# bcd_board.net
KiCad netlist of a schematic drawn in EAGLE
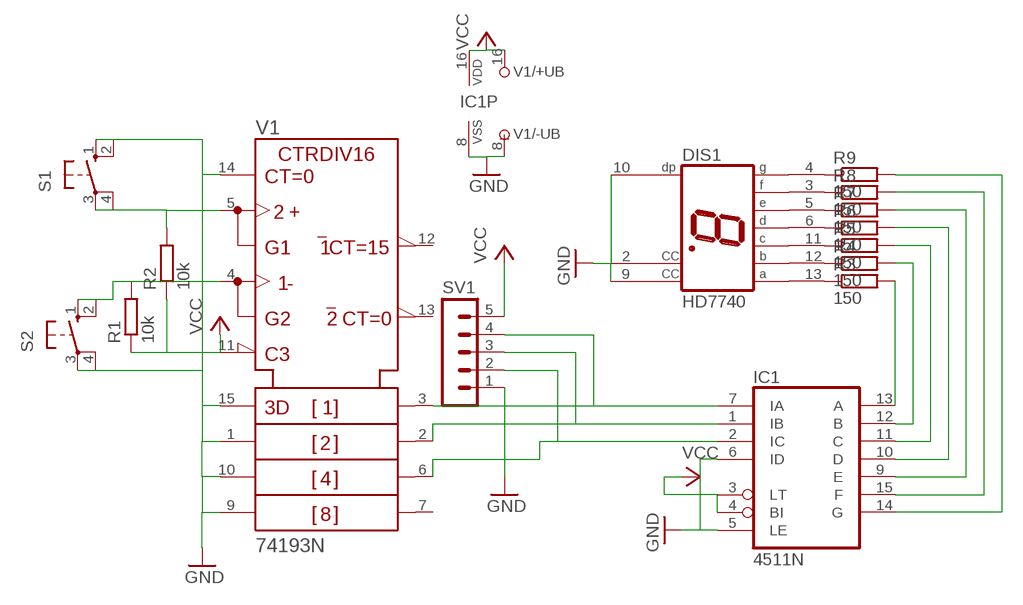
[diagram p0: schematic, sheet 1]

(export (version "E")
  (design (tool "Eeschema 10.0.6"))
  (components
    (comp (ref "DIS1")
      (value "HD7740")
      (footprint "eagle-import:HD7730")
      (libsource (lib "eagle-import") (part "HD7740"))
    )
    (comp (ref "IC1")
      (value "4511N")
      (footprint "eagle-import:DIL16")
      (libsource (lib "eagle-import") (part "4511N"))
    )
    (comp (ref "R1")
      (value "10k")
      (footprint "eagle-import:0204_7")
      (libsource (lib "eagle-import") (part "R-EU_0204/7"))
    )
    (comp (ref "R2")
      (value "10k")
      (footprint "eagle-import:0204_7")
      (libsource (lib "eagle-import") (part "R-EU_0204/7"))
    )
    (comp (ref "R3")
      (value "150")
      (footprint "eagle-import:0204_7")
      (libsource (lib "eagle-import") (part "R-EU_0204/7"))
    )
    (comp (ref "R4")
      (value "150")
      (footprint "eagle-import:0204_7")
      (libsource (lib "eagle-import") (part "R-EU_0204/7"))
    )
    (comp (ref "R5")
      (value "150")
      (footprint "eagle-import:0204_7")
      (libsource (lib "eagle-import") (part "R-EU_0204/7"))
    )
    (comp (ref "R6")
      (value "150")
      (footprint "eagle-import:0204_7")
      (libsource (lib "eagle-import") (part "R-EU_0204/7"))
    )
    (comp (ref "R7")
      (value "150")
      (footprint "eagle-import:0204_7")
      (libsource (lib "eagle-import") (part "R-EU_0204/7"))
    )
    (comp (ref "R8")
      (value "150")
      (footprint "eagle-import:0204_7")
      (libsource (lib "eagle-import") (part "R-EU_0204/7"))
    )
    (comp (ref "R9")
      (value "150")
      (footprint "eagle-import:0204_7")
      (libsource (lib "eagle-import") (part "R-EU_0204/7"))
    )
    (comp (ref "S1")
      (value "10-XX")
      (footprint "eagle-import:B3F-10XX")
      (fields (field (name "MPN") "B3F-1000"))
      (libsource (lib "eagle-import") (part "10-XX"))
    )
    (comp (ref "S2")
      (value "10-XX")
      (footprint "eagle-import:B3F-10XX")
      (fields (field (name "MPN") "B3F-1000"))
      (libsource (lib "eagle-import") (part "10-XX"))
    )
    (comp (ref "SV1")
      (value "MA05-1")
      (footprint "eagle-import:MA05-1")
      (libsource (lib "eagle-import") (part "MA05-1"))
    )
    (comp (ref "V1")
      (value "74193N")
      (footprint "eagle-import:DIL16")
      (libsource (lib "eagle-import") (part "74193N"))
    )
  )
  (nets
    (net (code "1") (name "GND") (class "Default")
      (node (ref "DIS1") (pin "10") (pinfunction "DP_10") (pintype "passive"))
      (node (ref "DIS1") (pin "2") (pinfunction "CC_2") (pintype "passive"))
      (node (ref "DIS1") (pin "9") (pinfunction "CC_9") (pintype "passive"))
      (node (ref "IC1") (pin "5") (pinfunction "LE_5") (pintype "input"))
      (node (ref "IC1") (pin "6") (pinfunction "ID_6") (pintype "input"))
      (node (ref "IC1") (pin "8") (pinfunction "VSS_8") (pintype "power_in"))
      (node (ref "S1") (pin "1") (pinfunction "S_1") (pintype "passive"))
      (node (ref "S1") (pin "2") (pinfunction "S1_2") (pintype "passive"))
      (node (ref "S2") (pin "3") (pinfunction "P_3") (pintype "passive"))
      (node (ref "S2") (pin "4") (pinfunction "P1_4") (pintype "passive"))
      (node (ref "SV1") (pin "1") (pinfunction "1_1") (pintype "passive"))
      (node (ref "V1") (pin "1") (pinfunction "B_1") (pintype "input"))
      (node (ref "V1") (pin "10") (pinfunction "C_10") (pintype "input"))
      (node (ref "V1") (pin "14") (pinfunction "CLR_14") (pintype "input"))
      (node (ref "V1") (pin "15") (pinfunction "A_15") (pintype "input"))
      (node (ref "V1") (pin "8") (pinfunction "-UB_8") (pintype "power_in"))
      (node (ref "V1") (pin "9") (pinfunction "D_9") (pintype "input"))
    )
    (net (code "2") (name "Net-(DIS1-A)") (class "Default")
      (node (ref "DIS1") (pin "13") (pinfunction "A_13") (pintype "passive"))
      (node (ref "R3") (pin "1") (pinfunction "1_1") (pintype "passive"))
    )
    (net (code "3") (name "Net-(DIS1-B)") (class "Default")
      (node (ref "DIS1") (pin "12") (pinfunction "B_12") (pintype "passive"))
      (node (ref "R4") (pin "1") (pinfunction "1_1") (pintype "passive"))
    )
    (net (code "4") (name "Net-(DIS1-C)") (class "Default")
      (node (ref "DIS1") (pin "11") (pinfunction "C_11") (pintype "passive"))
      (node (ref "R5") (pin "1") (pinfunction "1_1") (pintype "passive"))
    )
    (net (code "5") (name "Net-(DIS1-D)") (class "Default")
      (node (ref "DIS1") (pin "6") (pinfunction "D_6") (pintype "passive"))
      (node (ref "R6") (pin "1") (pinfunction "1_1") (pintype "passive"))
    )
    (net (code "6") (name "Net-(DIS1-E)") (class "Default")
      (node (ref "DIS1") (pin "5") (pinfunction "E_5") (pintype "passive"))
      (node (ref "R7") (pin "1") (pinfunction "1_1") (pintype "passive"))
    )
    (net (code "7") (name "Net-(DIS1-F)") (class "Default")
      (node (ref "DIS1") (pin "3") (pinfunction "F_3") (pintype "passive"))
      (node (ref "R8") (pin "1") (pinfunction "1_1") (pintype "passive"))
    )
    (net (code "8") (name "Net-(DIS1-G)") (class "Default")
      (node (ref "DIS1") (pin "4") (pinfunction "G_4") (pintype "passive"))
      (node (ref "R9") (pin "1") (pinfunction "1_1") (pintype "passive"))
    )
    (net (code "9") (name "Net-(IC1A-A)") (class "Default")
      (node (ref "IC1") (pin "13") (pinfunction "A_13") (pintype "output"))
      (node (ref "R3") (pin "2") (pinfunction "2_2") (pintype "passive"))
    )
    (net (code "10") (name "Net-(IC1A-B)") (class "Default")
      (node (ref "IC1") (pin "12") (pinfunction "B_12") (pintype "output"))
      (node (ref "R4") (pin "2") (pinfunction "2_2") (pintype "passive"))
    )
    (net (code "11") (name "Net-(IC1A-C)") (class "Default")
      (node (ref "IC1") (pin "11") (pinfunction "C_11") (pintype "output"))
      (node (ref "R5") (pin "2") (pinfunction "2_2") (pintype "passive"))
    )
    (net (code "12") (name "Net-(IC1A-D)") (class "Default")
      (node (ref "IC1") (pin "10") (pinfunction "D_10") (pintype "output"))
      (node (ref "R6") (pin "2") (pinfunction "2_2") (pintype "passive"))
    )
    (net (code "13") (name "Net-(IC1A-E)") (class "Default")
      (node (ref "IC1") (pin "9") (pinfunction "E_9") (pintype "output"))
      (node (ref "R7") (pin "2") (pinfunction "2_2") (pintype "passive"))
    )
    (net (code "14") (name "Net-(IC1A-F)") (class "Default")
      (node (ref "IC1") (pin "15") (pinfunction "F_15") (pintype "output"))
      (node (ref "R8") (pin "2") (pinfunction "2_2") (pintype "passive"))
    )
    (net (code "15") (name "Net-(IC1A-G)") (class "Default")
      (node (ref "IC1") (pin "14") (pinfunction "G_14") (pintype "output"))
      (node (ref "R9") (pin "2") (pinfunction "2_2") (pintype "passive"))
    )
    (net (code "16") (name "Net-(IC1A-IA)") (class "Default")
      (node (ref "IC1") (pin "7") (pinfunction "IA_7") (pintype "input"))
      (node (ref "SV1") (pin "4") (pinfunction "4_4") (pintype "passive"))
      (node (ref "V1") (pin "3") (pinfunction "QA_3") (pintype "output"))
    )
    (net (code "17") (name "Net-(IC1A-IB)") (class "Default")
      (node (ref "IC1") (pin "1") (pinfunction "IB_1") (pintype "input"))
      (node (ref "SV1") (pin "3") (pinfunction "3_3") (pintype "passive"))
      (node (ref "V1") (pin "2") (pinfunction "QB_2") (pintype "output"))
    )
    (net (code "18") (name "Net-(IC1A-IC)") (class "Default")
      (node (ref "IC1") (pin "2") (pinfunction "IC_2") (pintype "input"))
      (node (ref "SV1") (pin "2") (pinfunction "2_2") (pintype "passive"))
      (node (ref "V1") (pin "6") (pinfunction "QC_6") (pintype "output"))
    )
    (net (code "19") (name "Net-(S1-P)") (class "Default")
      (node (ref "R2") (pin "2") (pinfunction "2_2") (pintype "passive"))
      (node (ref "S1") (pin "3") (pinfunction "P_3") (pintype "passive"))
      (node (ref "S1") (pin "4") (pinfunction "P1_4") (pintype "passive"))
      (node (ref "V1") (pin "5") (pinfunction "UP_5") (pintype "input"))
    )
    (net (code "20") (name "Net-(S2-S)") (class "Default")
      (node (ref "R1") (pin "2") (pinfunction "2_2") (pintype "passive"))
      (node (ref "S2") (pin "1") (pinfunction "S_1") (pintype "passive"))
      (node (ref "S2") (pin "2") (pinfunction "S1_2") (pintype "passive"))
      (node (ref "V1") (pin "4") (pinfunction "DOWN_4") (pintype "input"))
    )
    (net (code "21") (name "VCC") (class "Default")
      (node (ref "IC1") (pin "16") (pinfunction "VDD_16") (pintype "power_in"))
      (node (ref "IC1") (pin "3") (pinfunction "LT_3") (pintype "input"))
      (node (ref "IC1") (pin "4") (pinfunction "BI_4") (pintype "input"))
      (node (ref "R1") (pin "1") (pinfunction "1_1") (pintype "passive"))
      (node (ref "R2") (pin "1") (pinfunction "1_1") (pintype "passive"))
      (node (ref "SV1") (pin "5") (pinfunction "5_5") (pintype "passive"))
      (node (ref "V1") (pin "11") (pinfunction "~{LOAD}_11") (pintype "input"))
      (node (ref "V1") (pin "16") (pinfunction "+UB_16") (pintype "power_in"))
    )
    (net (code "22") (name "unconnected-(V1C-QD-Pad7)") (class "Default")
      (node (ref "V1") (pin "7") (pinfunction "QD_7") (pintype "output"))
    )
    (net (code "23") (name "unconnected-(V1C-~{BO}-Pad13)") (class "Default")
      (node (ref "V1") (pin "13") (pinfunction "~{BO}_13") (pintype "output"))
    )
    (net (code "24") (name "unconnected-(V1C-~{CO}-Pad12)") (class "Default")
      (node (ref "V1") (pin "12") (pinfunction "~{CO}_12") (pintype "output"))
    )
  )
)
